# CH2-Isolation.net
KiCad netlist of a schematic drawn in Altium Designer
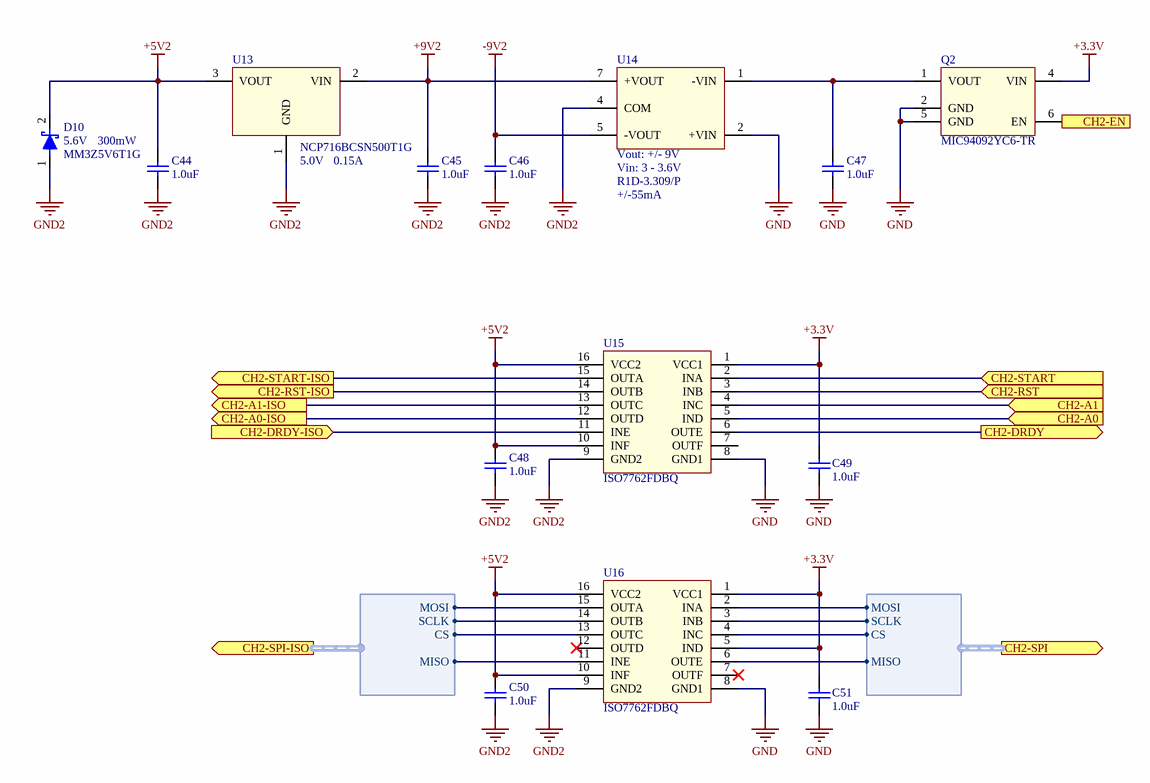
[diagram p0: CH2-Isolation.SchDoc]

(export (version "E")
  (design (tool "Eeschema 10.0.6"))
  (components
    (comp (ref "C44")
      (value "1.0uF")
      (footprint "CAP-0603")
      (description "CAP CER 1uF 25V X7R 0603")
      (fields (field (name "PARTNUMBER") "C0603C105M3RAC7867") (field (name "MANUFACTURER") "Kemet"))
      (libsource (lib "Kemet") (part "C0603C105M3RAC7867"))
    )
    (comp (ref "C45")
      (value "1.0uF")
      (footprint "CAP-0603")
      (description "CAP CER 1uF 25V X7R 0603")
      (fields (field (name "PARTNUMBER") "C0603C105M3RAC7867") (field (name "MANUFACTURER") "Kemet"))
      (libsource (lib "Kemet") (part "C0603C105M3RAC7867"))
    )
    (comp (ref "C46")
      (value "1.0uF")
      (footprint "CAP-0603")
      (description "CAP CER 1uF 25V X7R 0603")
      (fields (field (name "PARTNUMBER") "C0603C105M3RAC7867") (field (name "MANUFACTURER") "Kemet"))
      (libsource (lib "Kemet") (part "C0603C105M3RAC7867"))
    )
    (comp (ref "C47")
      (value "1.0uF")
      (footprint "CAP-0603")
      (description "CAP CER 1uF 25V X7R 0603")
      (fields (field (name "PARTNUMBER") "C0603C105M3RAC7867") (field (name "MANUFACTURER") "Kemet"))
      (libsource (lib "Kemet") (part "C0603C105M3RAC7867"))
    )
    (comp (ref "C48")
      (value "1.0uF")
      (footprint "CAP-0603")
      (description "CAP CER 1uF 25V X7R 0603")
      (fields (field (name "PARTNUMBER") "C0603C105M3RAC7867") (field (name "MANUFACTURER") "Kemet"))
      (libsource (lib "Kemet") (part "C0603C105M3RAC7867"))
    )
    (comp (ref "C49")
      (value "1.0uF")
      (footprint "CAP-0603")
      (description "CAP CER 1uF 25V X7R 0603")
      (fields (field (name "PARTNUMBER") "C0603C105M3RAC7867") (field (name "MANUFACTURER") "Kemet"))
      (libsource (lib "Kemet") (part "C0603C105M3RAC7867"))
    )
    (comp (ref "C50")
      (value "1.0uF")
      (footprint "CAP-0603")
      (description "CAP CER 1uF 25V X7R 0603")
      (fields (field (name "PARTNUMBER") "C0603C105M3RAC7867") (field (name "MANUFACTURER") "Kemet"))
      (libsource (lib "Kemet") (part "C0603C105M3RAC7867"))
    )
    (comp (ref "C51")
      (value "1.0uF")
      (footprint "CAP-0603")
      (description "CAP CER 1uF 25V X7R 0603")
      (fields (field (name "PARTNUMBER") "C0603C105M3RAC7867") (field (name "MANUFACTURER") "Kemet"))
      (libsource (lib "Kemet") (part "C0603C105M3RAC7867"))
    )
    (comp (ref "D10")
      (value "MM3Z5V6T1G")
      (footprint "SOD323 - DIODE UNIDIR")
      (description "Schottky Diode 30V 200mA SOT323")
      (fields
        (field (name "MANUFACTURER") "OnSemiconductor")
        (field (name "POWER") "300mW")
        (field (name "VZ") "5.6V")
        (field (name "PARTNUMBER") "MM3Z5V6T1G")
      )
      (libsource (lib "OnSemiconductors") (part "MM3Z5V6T1G"))
    )
    (comp (ref "Q2")
      (value "MIC94092YC6-TR")
      (footprint "TSSOP6")
      (fields (field (name "MANUFACTURER") "Microchip") (field (name "PARTNUMBER") "MIC94092YC6-TR"))
      (libsource (lib "Microchip") (part "MIC94092YC6-TR"))
    )
    (comp (ref "U13")
      (value "NCP716BCSN500T1G")
      (footprint "SOT23-5")
      (description "IC REG LDO 0.5V 0.15A TSOT23-5")
      (fields
        (field (name "MANUFACTURER") "ON Semiconductor")
        (field (name "PARTNUMBER") "NCP716BCSN500T1G")
        (field (name "VOLTAGE") "5.0V")
        (field (name "CURRENT") "0.15A")
      )
      (libsource (lib "OnSemiconductors") (part "NCP716BCSN500T1G"))
    )
    (comp (ref "U14")
      (value "R1D-3.309/P")
      (footprint "RECOM-R1D")
      (description "DC DC CONVERTER +/-9V 1W")
      (fields
        (field (name "MANUFACTURER") "Recom")
        (field (name "VOUT") "+/- 9V")
        (field (name "VIN") "3 - 3.6V")
        (field (name "PART NUMBER") "R1D-3.309/P")
        (field (name "CURRENT") "+/-55mA")
      )
      (libsource (lib "Recom") (part "R1D-3.309/P"))
    )
    (comp (ref "U15")
      (value "ISO7762FDBQ")
      (footprint "SSOP16")
      (description "Digital Isolator, six-channel, 4/2, 16-SSOP")
      (fields (field (name "MANUFACTURER") "Texas Instruments") (field (name "PARTNUMBER") "ISO7762FDBQ"))
      (libsource (lib "TexasInstruments") (part "ISO7762FDBQ"))
    )
    (comp (ref "U16")
      (value "ISO7762FDBQ")
      (footprint "SSOP16")
      (description "Digital Isolator, six-channel, 4/2, 16-SSOP")
      (fields (field (name "MANUFACTURER") "Texas Instruments") (field (name "PARTNUMBER") "ISO7762FDBQ"))
      (libsource (lib "TexasInstruments") (part "ISO7762FDBQ"))
    )
  )
  (nets
    (net (code "3") (name "+3.3V") (class "Default")
      (node (ref "C49") (pin "2") (pinfunction "2_2") (pintype "passive"))
      (node (ref "C51") (pin "2") (pinfunction "2_2") (pintype "passive"))
      (node (ref "Q2") (pin "4") (pinfunction "VIN_4") (pintype "passive"))
      (node (ref "U15") (pin "1") (pinfunction "VCC1_1") (pintype "passive"))
      (node (ref "U16") (pin "1") (pinfunction "VCC1_1") (pintype "passive"))
      (node (ref "U16") (pin "5") (pinfunction "IND_5") (pintype "passive"))
    )
    (net (code "4") (name "+5V2") (class "Default")
      (node (ref "C44") (pin "2") (pinfunction "2_2") (pintype "passive"))
      (node (ref "C48") (pin "2") (pinfunction "2_2") (pintype "passive"))
      (node (ref "C50") (pin "2") (pinfunction "2_2") (pintype "passive"))
      (node (ref "D10") (pin "2") (pinfunction "K_2") (pintype "passive"))
      (node (ref "U13") (pin "3") (pinfunction "VOUT_3") (pintype "passive"))
      (node (ref "U15") (pin "10") (pinfunction "INF_10") (pintype "passive"))
      (node (ref "U15") (pin "16") (pinfunction "VCC2_16") (pintype "passive"))
      (node (ref "U16") (pin "10") (pinfunction "INF_10") (pintype "passive"))
      (node (ref "U16") (pin "16") (pinfunction "VCC2_16") (pintype "passive"))
    )
    (net (code "5") (name "+9V2") (class "Default")
      (node (ref "C45") (pin "2") (pinfunction "2_2") (pintype "passive"))
      (node (ref "U13") (pin "2") (pinfunction "VIN_2") (pintype "passive"))
      (node (ref "U14") (pin "7") (pinfunction "+VOUT_7") (pintype "passive"))
    )
    (net (code "6") (name "-9V2") (class "Default")
      (node (ref "C46") (pin "2") (pinfunction "2_2") (pintype "passive"))
      (node (ref "U14") (pin "5") (pinfunction "-VOUT_5") (pintype "passive"))
    )
    (net (code "7") (name "/CH2-A0") (class "Default")
      (node (ref "U15") (pin "5") (pinfunction "IND_5") (pintype "passive"))
    )
    (net (code "8") (name "/CH2-A0-ISO") (class "Default")
      (node (ref "U15") (pin "12") (pinfunction "OUTD_12") (pintype "passive"))
    )
    (net (code "9") (name "/CH2-A1") (class "Default")
      (node (ref "U15") (pin "4") (pinfunction "INC_4") (pintype "passive"))
    )
    (net (code "10") (name "/CH2-A1-ISO") (class "Default")
      (node (ref "U15") (pin "13") (pinfunction "OUTC_13") (pintype "passive"))
    )
    (net (code "11") (name "/CH2-DRDY") (class "Default")
      (node (ref "U15") (pin "6") (pinfunction "OUTE_6") (pintype "passive"))
    )
    (net (code "12") (name "/CH2-DRDY-ISO") (class "Default")
      (node (ref "U15") (pin "11") (pinfunction "INE_11") (pintype "passive"))
    )
    (net (code "13") (name "/CH2-EN") (class "Default")
      (node (ref "Q2") (pin "6") (pinfunction "EN_6") (pintype "passive"))
    )
    (net (code "14") (name "/CH2-RST") (class "Default")
      (node (ref "U15") (pin "3") (pinfunction "INB_3") (pintype "passive"))
    )
    (net (code "15") (name "/CH2-RST-ISO") (class "Default")
      (node (ref "U15") (pin "14") (pinfunction "OUTB_14") (pintype "passive"))
    )
    (net (code "16") (name "/CH2-START") (class "Default")
      (node (ref "U15") (pin "2") (pinfunction "INA_2") (pintype "passive"))
    )
    (net (code "17") (name "/CH2-START-ISO") (class "Default")
      (node (ref "U15") (pin "15") (pinfunction "OUTA_15") (pintype "passive"))
    )
    (net (code "20") (name "GND") (class "Default")
      (node (ref "C47") (pin "1") (pinfunction "1_1") (pintype "passive"))
      (node (ref "C49") (pin "1") (pinfunction "1_1") (pintype "passive"))
      (node (ref "C51") (pin "1") (pinfunction "1_1") (pintype "passive"))
      (node (ref "Q2") (pin "2") (pinfunction "GND_2") (pintype "passive"))
      (node (ref "Q2") (pin "5") (pinfunction "GND_5") (pintype "passive"))
      (node (ref "U14") (pin "2") (pinfunction "+VIN_2") (pintype "passive"))
      (node (ref "U15") (pin "8") (pinfunction "GND1_8") (pintype "passive"))
      (node (ref "U16") (pin "8") (pinfunction "GND1_8") (pintype "passive"))
    )
    (net (code "21") (name "GND2") (class "Default")
      (node (ref "C44") (pin "1") (pinfunction "1_1") (pintype "passive"))
      (node (ref "C45") (pin "1") (pinfunction "1_1") (pintype "passive"))
      (node (ref "C46") (pin "1") (pinfunction "1_1") (pintype "passive"))
      (node (ref "C48") (pin "1") (pinfunction "1_1") (pintype "passive"))
      (node (ref "C50") (pin "1") (pinfunction "1_1") (pintype "passive"))
      (node (ref "D10") (pin "1") (pinfunction "A_1") (pintype "passive"))
      (node (ref "U13") (pin "1") (pinfunction "GND_1") (pintype "passive"))
      (node (ref "U14") (pin "4") (pinfunction "COM_4") (pintype "passive"))
      (node (ref "U15") (pin "9") (pinfunction "GND2_9") (pintype "passive"))
      (node (ref "U16") (pin "9") (pinfunction "GND2_9") (pintype "passive"))
    )
    (net (code "22") (name "Net-(Q2-VOUT)") (class "Default")
      (node (ref "C47") (pin "2") (pinfunction "2_2") (pintype "passive"))
      (node (ref "Q2") (pin "1") (pinfunction "VOUT_1") (pintype "passive"))
      (node (ref "U14") (pin "1") (pinfunction "-VIN_1") (pintype "passive"))
    )
    (net (code "23") (name "unconnected-(U15-OUTF-Pad7)") (class "Default")
      (node (ref "U15") (pin "7") (pinfunction "OUTF_7") (pintype "passive"))
    )
    (net (code "24") (name "unconnected-(U16-INA-Pad2)") (class "Default")
      (node (ref "U16") (pin "2") (pinfunction "INA_2") (pintype "passive"))
    )
    (net (code "25") (name "unconnected-(U16-INB-Pad3)") (class "Default")
      (node (ref "U16") (pin "3") (pinfunction "INB_3") (pintype "passive"))
    )
    (net (code "26") (name "unconnected-(U16-INC-Pad4)") (class "Default")
      (node (ref "U16") (pin "4") (pinfunction "INC_4") (pintype "passive"))
    )
    (net (code "27") (name "unconnected-(U16-INE-Pad11)") (class "Default")
      (node (ref "U16") (pin "11") (pinfunction "INE_11") (pintype "passive"))
    )
    (net (code "28") (name "unconnected-(U16-OUTA-Pad15)") (class "Default")
      (node (ref "U16") (pin "15") (pinfunction "OUTA_15") (pintype "passive"))
    )
    (net (code "29") (name "unconnected-(U16-OUTB-Pad14)") (class "Default")
      (node (ref "U16") (pin "14") (pinfunction "OUTB_14") (pintype "passive"))
    )
    (net (code "30") (name "unconnected-(U16-OUTC-Pad13)") (class "Default")
      (node (ref "U16") (pin "13") (pinfunction "OUTC_13") (pintype "passive"))
    )
    (net (code "31") (name "unconnected-(U16-OUTD-Pad12)") (class "Default")
      (node (ref "U16") (pin "12") (pinfunction "OUTD_12") (pintype "passive+no_connect"))
    )
    (net (code "32") (name "unconnected-(U16-OUTE-Pad6)") (class "Default")
      (node (ref "U16") (pin "6") (pinfunction "OUTE_6") (pintype "passive"))
    )
    (net (code "33") (name "unconnected-(U16-OUTF-Pad7)") (class "Default")
      (node (ref "U16") (pin "7") (pinfunction "OUTF_7") (pintype "passive+no_connect"))
    )
  )
)
